# STM32G070RBT6.net
KiCad netlist of a schematic drawn in Altium Designer
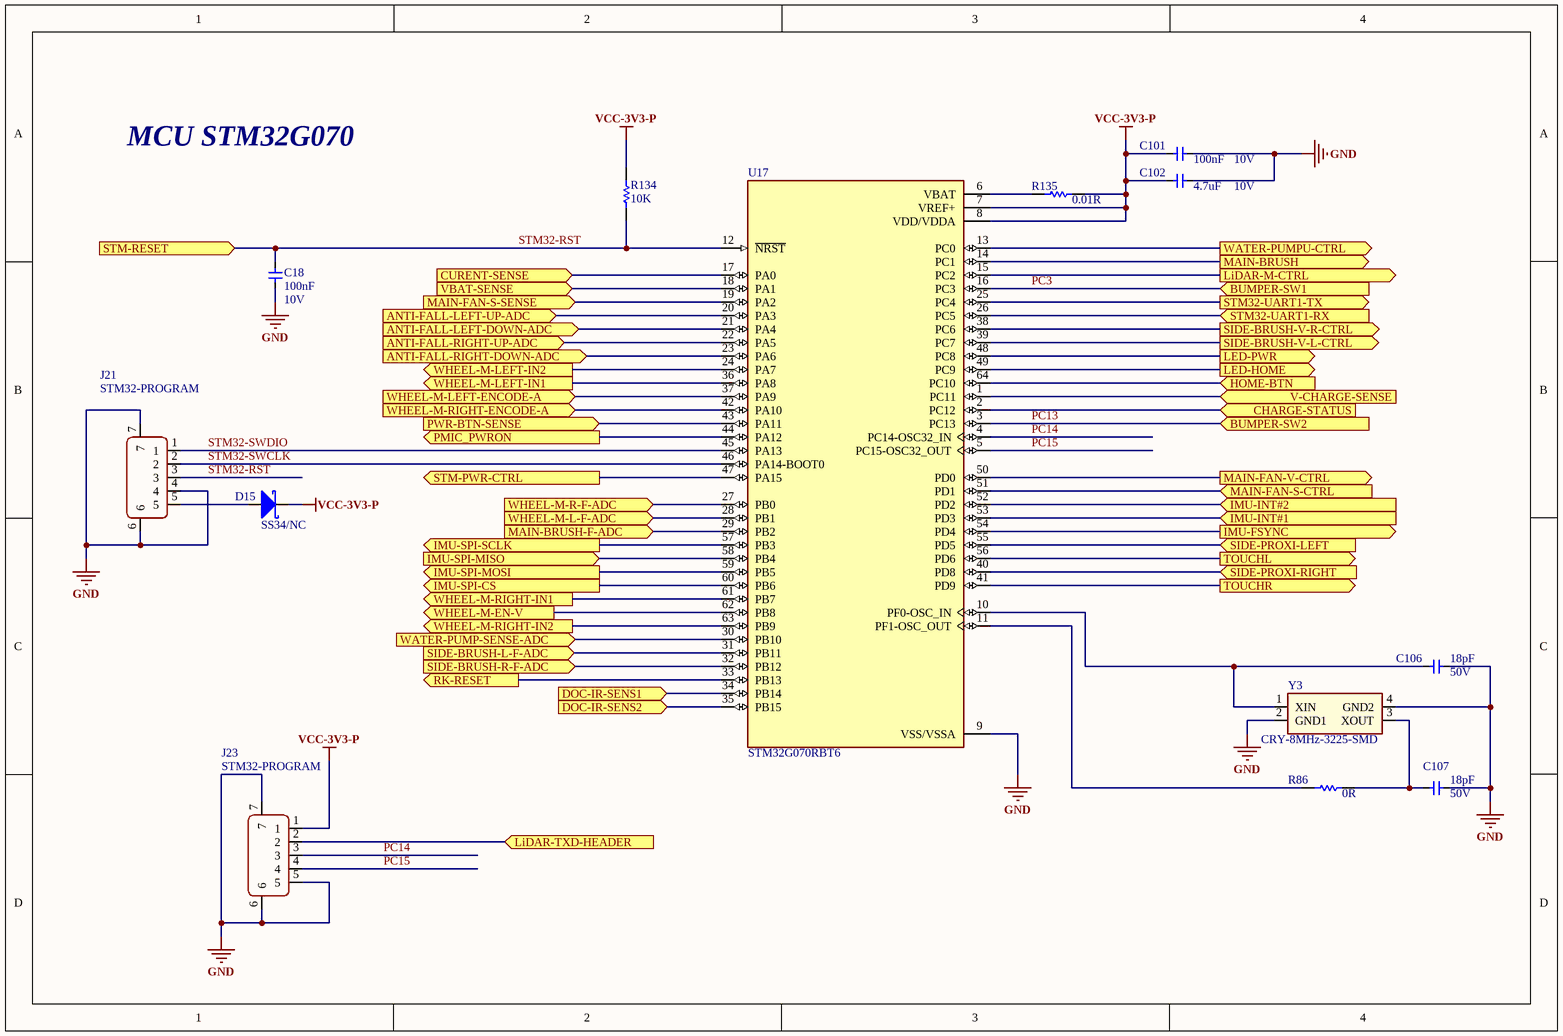
[diagram p0: STM32G070RBT6.SchDoc]

(export (version "E")
  (design (tool "Eeschema 10.0.6"))
  (components
    (comp (ref "C18")
      (value "100nF")
      (footprint "CAP-0402")
      (fields (field (name "VOLTAGERATE") "10V"))
      (libsource (lib "DesignLibrary") (part "Capacitor-1"))
    )
    (comp (ref "C101")
      (value "100nF")
      (footprint "CAP-0402")
      (fields (field (name "VOLTAGERATE") "10V"))
      (libsource (lib "DesignLibrary") (part "Capacitor-1"))
    )
    (comp (ref "C102")
      (value "4.7uF")
      (footprint "CAP-0603")
      (fields (field (name "VOLTAGERATE") "10V"))
      (libsource (lib "DesignLibrary") (part "Capacitor-1"))
    )
    (comp (ref "C106")
      (value "18pF")
      (footprint "CAP-0402")
      (fields (field (name "VOLTAGERATE") "50V"))
      (libsource (lib "DesignLibrary") (part "Capacitor-1"))
    )
    (comp (ref "C107")
      (value "18pF")
      (footprint "CAP-0402")
      (fields (field (name "VOLTAGERATE") "50V"))
      (libsource (lib "DesignLibrary") (part "Capacitor-1"))
    )
    (comp (ref "D15") (value "SS34/NC") (footprint "SMA") (libsource (lib "DesignLibrary") (part "DIODE-2")))
    (comp (ref "J21")
      (value "STM32-PROGRAM")
      (footprint "HDR1X5")
      (libsource (lib "DesignLibrary") (part "HDRx5"))
    )
    (comp (ref "J23")
      (value "STM32-PROGRAM")
      (footprint "HDR1X5")
      (libsource (lib "DesignLibrary") (part "HDRx5"))
    )
    (comp (ref "R86")
      (value "0R")
      (footprint "RES-0402")
      (libsource (lib "DesignLibrary") (part "Resistor-1"))
    )
    (comp (ref "R134")
      (value "10K")
      (footprint "RES-0402")
      (libsource (lib "DesignLibrary") (part "Resistor-1"))
    )
    (comp (ref "R135")
      (value "0.01R")
      (footprint "RES-0805-S")
      (libsource (lib "DesignLibrary") (part "Resistor-1"))
    )
    (comp (ref "U17")
      (value "STM32G070RBT6")
      (footprint "QFP50P1200X1200X160-64N")
      (libsource (lib "DesignLibrary") (part "STM32G070RBT6"))
    )
    (comp (ref "Y3")
      (value "CRY-8MHz-3225-SMD")
      (footprint "X4B250_320H120_SMD")
      (libsource (lib "DesignLibrary") (part "CRY-24MHz-3225-SMD_0"))
    )
  )
  (nets
    (net (code "1") (name "/ANTI-FALL-LEFT-DOWN-ADC") (class "Default")
      (node (ref "U17") (pin "21") (pinfunction "PA4_21") (pintype "bidirectional"))
    )
    (net (code "2") (name "/ANTI-FALL-LEFT-UP-ADC") (class "Default")
      (node (ref "U17") (pin "20") (pinfunction "PA3_20") (pintype "bidirectional"))
    )
    (net (code "3") (name "/ANTI-FALL-RIGHT-DOWN-ADC") (class "Default")
      (node (ref "U17") (pin "23") (pinfunction "PA6_23") (pintype "bidirectional"))
    )
    (net (code "4") (name "/ANTI-FALL-RIGHT-UP-ADC") (class "Default")
      (node (ref "U17") (pin "22") (pinfunction "PA5_22") (pintype "bidirectional"))
    )
    (net (code "5") (name "/CHARGE-STATUS") (class "Default")
      (node (ref "U17") (pin "2") (pinfunction "PC12_2") (pintype "bidirectional"))
    )
    (net (code "6") (name "/CURENT-SENSE") (class "Default")
      (node (ref "U17") (pin "17") (pinfunction "PA0_17") (pintype "bidirectional"))
    )
    (net (code "7") (name "/DOC-IR-SENS1") (class "Default")
      (node (ref "U17") (pin "34") (pinfunction "PB14_34") (pintype "bidirectional"))
    )
    (net (code "8") (name "/DOC-IR-SENS2") (class "Default")
      (node (ref "U17") (pin "35") (pinfunction "PB15_35") (pintype "bidirectional"))
    )
    (net (code "9") (name "/HOME-BTN") (class "Default")
      (node (ref "U17") (pin "64") (pinfunction "PC10_64") (pintype "bidirectional"))
    )
    (net (code "10") (name "/IMU-FSYNC") (class "Default")
      (node (ref "U17") (pin "54") (pinfunction "PD4_54") (pintype "bidirectional"))
    )
    (net (code "11") (name "/IMU-INT#1") (class "Default")
      (node (ref "U17") (pin "53") (pinfunction "PD3_53") (pintype "bidirectional"))
    )
    (net (code "12") (name "/IMU-INT#2") (class "Default")
      (node (ref "U17") (pin "52") (pinfunction "PD2_52") (pintype "bidirectional"))
    )
    (net (code "13") (name "/IMU-SPI-CS") (class "Default")
      (node (ref "U17") (pin "60") (pinfunction "PB6_60") (pintype "bidirectional"))
    )
    (net (code "14") (name "/IMU-SPI-MISO") (class "Default")
      (node (ref "U17") (pin "58") (pinfunction "PB4_58") (pintype "bidirectional"))
    )
    (net (code "15") (name "/IMU-SPI-MOSI") (class "Default")
      (node (ref "U17") (pin "59") (pinfunction "PB5_59") (pintype "bidirectional"))
    )
    (net (code "16") (name "/IMU-SPI-SCLK") (class "Default")
      (node (ref "U17") (pin "57") (pinfunction "PB3_57") (pintype "bidirectional"))
    )
    (net (code "17") (name "/LED-HOME") (class "Default")
      (node (ref "U17") (pin "49") (pinfunction "PC9_49") (pintype "bidirectional"))
    )
    (net (code "18") (name "/LED-PWR") (class "Default")
      (node (ref "U17") (pin "48") (pinfunction "PC8_48") (pintype "bidirectional"))
    )
    (net (code "19") (name "/LiDAR-M-CTRL") (class "Default")
      (node (ref "U17") (pin "15") (pinfunction "PC2_15") (pintype "bidirectional"))
    )
    (net (code "20") (name "/LiDAR-TXD-HEADER") (class "Default")
      (node (ref "J23") (pin "2") (pinfunction "2_2") (pintype "passive"))
    )
    (net (code "21") (name "/MAIN-BRUSH") (class "Default")
      (node (ref "U17") (pin "14") (pinfunction "PC1_14") (pintype "bidirectional"))
    )
    (net (code "22") (name "/MAIN-BRUSH-F-ADC") (class "Default")
      (node (ref "U17") (pin "29") (pinfunction "PB2_29") (pintype "bidirectional"))
    )
    (net (code "23") (name "/MAIN-FAN-S-CTRL") (class "Default")
      (node (ref "U17") (pin "51") (pinfunction "PD1_51") (pintype "bidirectional"))
    )
    (net (code "24") (name "/MAIN-FAN-S-SENSE") (class "Default")
      (node (ref "U17") (pin "19") (pinfunction "PA2_19") (pintype "bidirectional"))
    )
    (net (code "25") (name "/MAIN-FAN-V-CTRL") (class "Default")
      (node (ref "U17") (pin "50") (pinfunction "PD0_50") (pintype "bidirectional"))
    )
    (net (code "26") (name "/PC3") (class "Default")
      (node (ref "U17") (pin "16") (pinfunction "PC3_16") (pintype "bidirectional"))
    )
    (net (code "27") (name "/PC13") (class "Default")
      (node (ref "U17") (pin "3") (pinfunction "PC13_3") (pintype "bidirectional"))
    )
    (net (code "28") (name "/PC14") (class "Default")
      (node (ref "J23") (pin "3") (pinfunction "3_3") (pintype "passive"))
      (node (ref "U17") (pin "4") (pinfunction "PC14-OSC32_IN_4") (pintype "bidirectional"))
    )
    (net (code "29") (name "/PC15") (class "Default")
      (node (ref "J23") (pin "4") (pinfunction "4_4") (pintype "passive"))
      (node (ref "U17") (pin "5") (pinfunction "PC15-OSC32_OUT_5") (pintype "bidirectional"))
    )
    (net (code "30") (name "/PMIC_PWRON") (class "Default")
      (node (ref "U17") (pin "44") (pinfunction "PA12_44") (pintype "bidirectional"))
    )
    (net (code "31") (name "/PWR-BTN-SENSE") (class "Default")
      (node (ref "U17") (pin "43") (pinfunction "PA11_43") (pintype "bidirectional"))
    )
    (net (code "32") (name "/RK-RESET") (class "Default")
      (node (ref "U17") (pin "33") (pinfunction "PB13_33") (pintype "bidirectional"))
    )
    (net (code "33") (name "/SIDE-BRUSH-L-F-ADC") (class "Default")
      (node (ref "U17") (pin "31") (pinfunction "PB11_31") (pintype "bidirectional"))
    )
    (net (code "34") (name "/SIDE-BRUSH-R-F-ADC") (class "Default")
      (node (ref "U17") (pin "32") (pinfunction "PB12_32") (pintype "bidirectional"))
    )
    (net (code "35") (name "/SIDE-BRUSH-V-L-CTRL") (class "Default")
      (node (ref "U17") (pin "39") (pinfunction "PC7_39") (pintype "bidirectional"))
    )
    (net (code "36") (name "/SIDE-BRUSH-V-R-CTRL") (class "Default")
      (node (ref "U17") (pin "38") (pinfunction "PC6_38") (pintype "bidirectional"))
    )
    (net (code "37") (name "/SIDE-PROXI-LEFT") (class "Default")
      (node (ref "U17") (pin "55") (pinfunction "PD5_55") (pintype "bidirectional"))
    )
    (net (code "38") (name "/SIDE-PROXI-RIGHT") (class "Default")
      (node (ref "U17") (pin "40") (pinfunction "PD8_40") (pintype "bidirectional"))
    )
    (net (code "39") (name "/STM-PWR-CTRL") (class "Default")
      (node (ref "U17") (pin "47") (pinfunction "PA15_47") (pintype "bidirectional"))
    )
    (net (code "40") (name "/STM32-RST") (class "Default")
      (node (ref "C18") (pin "1") (pinfunction "1_1") (pintype "passive"))
      (node (ref "J21") (pin "3") (pinfunction "3_3") (pintype "passive"))
      (node (ref "R134") (pin "2") (pintype "passive"))
      (node (ref "U17") (pin "12") (pinfunction "~{NRST}_12") (pintype "input"))
    )
    (net (code "41") (name "/STM32-SWCLK") (class "Default")
      (node (ref "J21") (pin "2") (pinfunction "2_2") (pintype "passive"))
      (node (ref "U17") (pin "46") (pinfunction "PA14-BOOT0_46") (pintype "bidirectional"))
    )
    (net (code "42") (name "/STM32-SWDIO") (class "Default")
      (node (ref "J21") (pin "1") (pinfunction "1_1") (pintype "passive"))
      (node (ref "U17") (pin "45") (pinfunction "PA13_45") (pintype "bidirectional"))
    )
    (net (code "43") (name "/STM32-UART1-RX") (class "Default")
      (node (ref "U17") (pin "26") (pinfunction "PC5_26") (pintype "bidirectional"))
    )
    (net (code "44") (name "/STM32-UART1-TX") (class "Default")
      (node (ref "U17") (pin "25") (pinfunction "PC4_25") (pintype "bidirectional"))
    )
    (net (code "45") (name "/TOUCHL") (class "Default")
      (node (ref "U17") (pin "56") (pinfunction "PD6_56") (pintype "bidirectional"))
    )
    (net (code "46") (name "/TOUCHR") (class "Default")
      (node (ref "U17") (pin "41") (pinfunction "PD9_41") (pintype "bidirectional"))
    )
    (net (code "47") (name "/V-CHARGE-SENSE") (class "Default")
      (node (ref "U17") (pin "1") (pinfunction "PC11_1") (pintype "bidirectional"))
    )
    (net (code "48") (name "/VBAT-SENSE") (class "Default")
      (node (ref "U17") (pin "18") (pinfunction "PA1_18") (pintype "bidirectional"))
    )
    (net (code "49") (name "/WATER-PUMP-SENSE-ADC") (class "Default")
      (node (ref "U17") (pin "30") (pinfunction "PB10_30") (pintype "bidirectional"))
    )
    (net (code "50") (name "/WATER-PUMPU-CTRL") (class "Default")
      (node (ref "U17") (pin "13") (pinfunction "PC0_13") (pintype "bidirectional"))
    )
    (net (code "51") (name "/WHEEL-M-EN-V") (class "Default")
      (node (ref "U17") (pin "62") (pinfunction "PB8_62") (pintype "bidirectional"))
    )
    (net (code "52") (name "/WHEEL-M-L-F-ADC") (class "Default")
      (node (ref "U17") (pin "28") (pinfunction "PB1_28") (pintype "bidirectional"))
    )
    (net (code "53") (name "/WHEEL-M-LEFT-ENCODE-A") (class "Default")
      (node (ref "U17") (pin "37") (pinfunction "PA9_37") (pintype "bidirectional"))
    )
    (net (code "54") (name "/WHEEL-M-LEFT-IN1") (class "Default")
      (node (ref "U17") (pin "36") (pinfunction "PA8_36") (pintype "bidirectional"))
    )
    (net (code "55") (name "/WHEEL-M-LEFT-IN2") (class "Default")
      (node (ref "U17") (pin "24") (pinfunction "PA7_24") (pintype "bidirectional"))
    )
    (net (code "56") (name "/WHEEL-M-R-F-ADC") (class "Default")
      (node (ref "U17") (pin "27") (pinfunction "PB0_27") (pintype "bidirectional"))
    )
    (net (code "57") (name "/WHEEL-M-RIGHT-ENCODE-A") (class "Default")
      (node (ref "U17") (pin "42") (pinfunction "PA10_42") (pintype "bidirectional"))
    )
    (net (code "58") (name "/WHEEL-M-RIGHT-IN1") (class "Default")
      (node (ref "U17") (pin "61") (pinfunction "PB7_61") (pintype "bidirectional"))
    )
    (net (code "59") (name "/WHEEL-M-RIGHT-IN2") (class "Default")
      (node (ref "U17") (pin "63") (pinfunction "PB9_63") (pintype "bidirectional"))
    )
    (net (code "60") (name "GND") (class "Default")
      (node (ref "C101") (pin "1") (pinfunction "1_1") (pintype "passive"))
      (node (ref "C102") (pin "1") (pinfunction "1_1") (pintype "passive"))
      (node (ref "C106") (pin "1") (pinfunction "1_1") (pintype "passive"))
      (node (ref "C107") (pin "1") (pinfunction "1_1") (pintype "passive"))
      (node (ref "C18") (pin "2") (pinfunction "2_2") (pintype "passive"))
      (node (ref "J21") (pin "4") (pinfunction "4_4") (pintype "passive"))
      (node (ref "J21") (pin "6") (pinfunction "6_6") (pintype "passive"))
      (node (ref "J21") (pin "7") (pinfunction "7_7") (pintype "passive"))
      (node (ref "J23") (pin "5") (pinfunction "5_5") (pintype "passive"))
      (node (ref "J23") (pin "6") (pinfunction "6_6") (pintype "passive"))
      (node (ref "J23") (pin "7") (pinfunction "7_7") (pintype "passive"))
      (node (ref "U17") (pin "9") (pinfunction "VSS/VSSA_9") (pintype "power_in"))
      (node (ref "Y3") (pin "2") (pinfunction "GND1_2") (pintype "passive"))
      (node (ref "Y3") (pin "4") (pinfunction "GND2_4") (pintype "passive"))
    )
    (net (code "61") (name "Net-(D15-A)") (class "Default")
      (node (ref "D15") (pin "1") (pinfunction "A_1") (pintype "passive"))
      (node (ref "J21") (pin "5") (pinfunction "5_5") (pintype "passive"))
    )
    (net (code "62") (name "Net-(U17-PF0-OSC_IN)") (class "Default")
      (node (ref "C106") (pin "2") (pinfunction "2_2") (pintype "passive"))
      (node (ref "U17") (pin "10") (pinfunction "PF0-OSC_IN_10") (pintype "bidirectional"))
      (node (ref "Y3") (pin "1") (pinfunction "XIN_1") (pintype "passive"))
    )
    (net (code "63") (name "Net-(U17-PF1-OSC_OUT)") (class "Default")
      (node (ref "R86") (pin "1") (pintype "passive"))
      (node (ref "U17") (pin "11") (pinfunction "PF1-OSC_OUT_11") (pintype "bidirectional"))
    )
    (net (code "64") (name "Net-(U17-VBAT)") (class "Default")
      (node (ref "R135") (pin "2") (pintype "passive"))
      (node (ref "U17") (pin "6") (pinfunction "VBAT_6") (pintype "power_in"))
    )
    (net (code "65") (name "Net-(Y3-XOUT)") (class "Default")
      (node (ref "C107") (pin "2") (pinfunction "2_2") (pintype "passive"))
      (node (ref "R86") (pin "2") (pintype "passive"))
      (node (ref "Y3") (pin "3") (pinfunction "XOUT_3") (pintype "passive"))
    )
    (net (code "66") (name "VCC-3V3-P") (class "Default")
      (node (ref "C101") (pin "2") (pinfunction "2_2") (pintype "passive"))
      (node (ref "C102") (pin "2") (pinfunction "2_2") (pintype "passive"))
      (node (ref "D15") (pin "2") (pinfunction "K_2") (pintype "passive"))
      (node (ref "J23") (pin "1") (pinfunction "1_1") (pintype "passive"))
      (node (ref "R134") (pin "1") (pintype "passive"))
      (node (ref "R135") (pin "1") (pintype "passive"))
      (node (ref "U17") (pin "7") (pinfunction "VREF+_7") (pintype "power_in"))
      (node (ref "U17") (pin "8") (pinfunction "VDD/VDDA_8") (pintype "power_in"))
    )
  )
)
